# DevBoard.net
KiCad netlist of a schematic drawn in Altium Designer
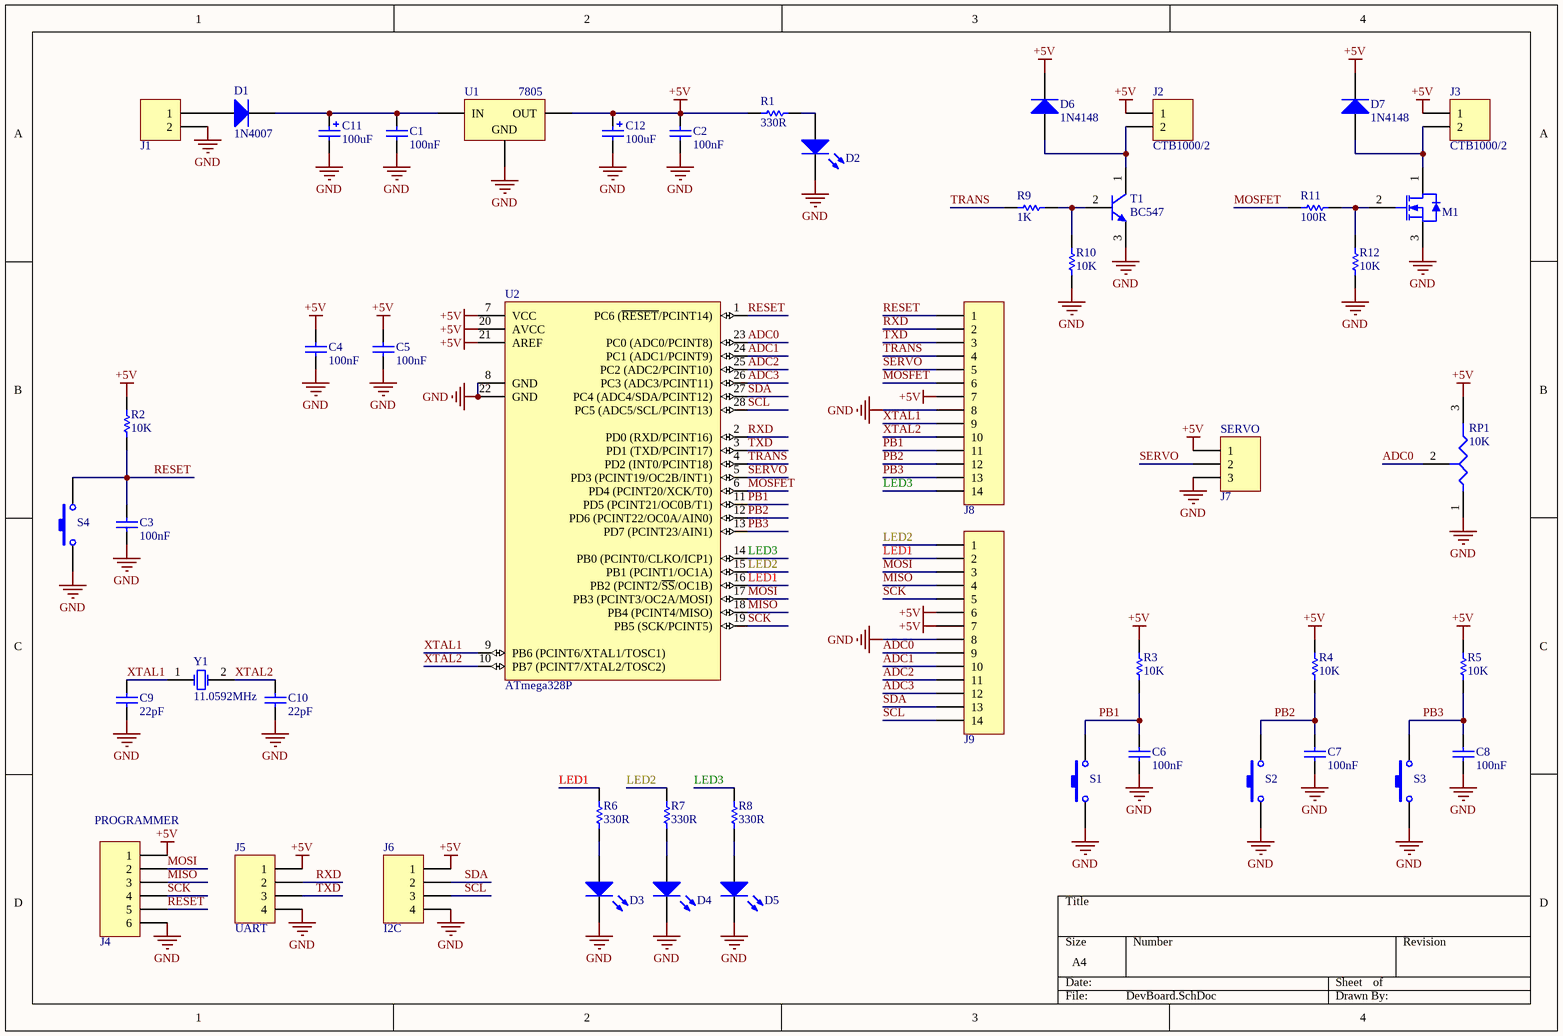
[diagram p0: DevBoard.SchDoc]

(export (version "E")
  (design (tool "Eeschema 10.0.6"))
  (components
    (comp (ref "C1")
      (value "100nF")
      (footprint "RAD-0.1")
      (description "Ceramic Capacitor")
      (libsource (lib "CapacitorsTH") (part "CAP"))
    )
    (comp (ref "C2")
      (value "100nF")
      (footprint "RAD-0.1")
      (description "Ceramic Capacitor")
      (libsource (lib "CapacitorsTH") (part "CAP"))
    )
    (comp (ref "C3")
      (value "100nF")
      (footprint "RAD-0.1")
      (description "Ceramic Capacitor")
      (libsource (lib "CapacitorsTH") (part "CAP"))
    )
    (comp (ref "C4")
      (value "100nF")
      (footprint "RAD-0.1")
      (description "Ceramic Capacitor")
      (libsource (lib "CapacitorsTH") (part "CAP"))
    )
    (comp (ref "C5")
      (value "100nF")
      (footprint "RAD-0.1")
      (description "Ceramic Capacitor")
      (libsource (lib "CapacitorsTH") (part "CAP"))
    )
    (comp (ref "C6")
      (value "100nF")
      (footprint "RAD-0.1")
      (description "Ceramic Capacitor")
      (libsource (lib "CapacitorsTH") (part "CAP"))
    )
    (comp (ref "C7")
      (value "100nF")
      (footprint "RAD-0.1")
      (description "Ceramic Capacitor")
      (libsource (lib "CapacitorsTH") (part "CAP"))
    )
    (comp (ref "C8")
      (value "100nF")
      (footprint "RAD-0.1")
      (description "Ceramic Capacitor")
      (libsource (lib "CapacitorsTH") (part "CAP"))
    )
    (comp (ref "C9")
      (value "22pF")
      (footprint "RAD-0.1")
      (description "Ceramic Capacitor")
      (libsource (lib "CapacitorsTH") (part "CAP"))
    )
    (comp (ref "C10")
      (value "22pF")
      (footprint "RAD-0.1")
      (description "Ceramic Capacitor")
      (libsource (lib "CapacitorsTH") (part "CAP"))
    )
    (comp (ref "C11")
      (value "100uF")
      (footprint "CAP3.5mmX8mm")
      (description "Electrolytic Capacitor")
      (libsource (lib "CapacitorsTH") (part "CAP POL"))
    )
    (comp (ref "C12")
      (value "100uF")
      (footprint "CAP3.5mmX8mm")
      (description "Electrolytic Capacitor")
      (libsource (lib "CapacitorsTH") (part "CAP POL"))
    )
    (comp (ref "D1")
      (value "1N4007")
      (footprint "DO-41")
      (description "Rectifier, 1A, 1000V")
      (libsource (lib "diode_regular") (part "1N4007"))
    )
    (comp (ref "D2")
      (value "Power ON")
      (footprint "LED3mmRED")
      (description "LED")
      (libsource (lib "LED_TH") (part "LED"))
    )
    (comp (ref "D3")
      (value "LED1")
      (footprint "LED3mmRED")
      (description "LED")
      (libsource (lib "LED_TH") (part "LED"))
    )
    (comp (ref "D4")
      (value "LED1")
      (footprint "LED3MMYELLOW")
      (description "LED")
      (libsource (lib "LED_TH") (part "LED"))
    )
    (comp (ref "D5")
      (value "LED1")
      (footprint "LED3MMGREEN")
      (description "LED")
      (libsource (lib "LED_TH") (part "LED"))
    )
    (comp (ref "D6")
      (value "1N4148")
      (footprint "DO-35")
      (description "High Conductance Fast Diode")
      (libsource (lib "diode_regular_20151016") (part "1N4148"))
    )
    (comp (ref "D7")
      (value "1N4148")
      (footprint "DO-35")
      (description "High Conductance Fast Diode")
      (libsource (lib "diode_regular_20151016") (part "1N4148"))
    )
    (comp (ref "J1")
      (value "CTB1000/2")
      (footprint "CTB1000/2")
      (description "CTB1000/2, PCB TERMINAL BLOCK, 5MM, 2WAY")
      (fields (field (name "MANUFACTURER") "CAMDENBOSS"))
      (libsource (lib "") (part "CTB1000/2_1"))
    )
    (comp (ref "J2")
      (value "CTB1000/2")
      (footprint "CTB1000/2")
      (description "CTB1000/2, PCB TERMINAL BLOCK, 5MM, 2WAY")
      (fields (field (name "MANUFACTURER") "CAMDENBOSS"))
      (libsource (lib "clamp_2pin_2015030") (part "CTB1000/2"))
    )
    (comp (ref "J3")
      (value "CTB1000/2")
      (footprint "CTB1000/2")
      (description "CTB1000/2, PCB TERMINAL BLOCK, 5MM, 2WAY")
      (fields (field (name "MANUFACTURER") "CAMDENBOSS"))
      (libsource (lib "clamp_2pin_2015030") (part "CTB1000/2"))
    )
    (comp (ref "J4")
      (value "PROGRAMMER")
      (footprint "HEADER1X6")
      (description "Header, 6-Pin, 1-row")
      (libsource (lib "Header_20150530") (part "HEADER1X6"))
    )
    (comp (ref "J5")
      (value "UART")
      (footprint "HEADER1X4")
      (description "Header, 4-Pin, 1-row")
      (libsource (lib "Header_20150530") (part "HEADER1X4"))
    )
    (comp (ref "J6")
      (value "I2C")
      (footprint "HEADER1X4")
      (description "Header, 4-Pin, 1-row")
      (libsource (lib "Header_20150530") (part "HEADER1X4"))
    )
    (comp (ref "J7")
      (value "SERVO")
      (footprint "HEADER1X3")
      (description "Header, 3-Pin, 1-row")
      (libsource (lib "Header_20150530") (part "HEADER1X3"))
    )
    (comp (ref "J8")
      (value "HEADER1X14")
      (footprint "HEADER1X14")
      (description "Header, 14-pin, 1-row")
      (libsource (lib "Header_20150530") (part "HEADER1X14"))
    )
    (comp (ref "J9")
      (value "HEADER1X14")
      (footprint "HEADER1X14")
      (description "Header, 14-pin, 1-row")
      (libsource (lib "Header_20150530") (part "HEADER1X14"))
    )
    (comp (ref "M1")
      (value "BS170")
      (footprint "TO-92")
      (description "N-Channel MOSFET")
      (libsource (lib "mosfets") (part "BS170"))
    )
    (comp (ref "R1") (value "330R") (footprint "AXIAL-0.3") (libsource (lib "ResistorsTH") (part "Resistor")))
    (comp (ref "R2") (value "10K") (footprint "AXIAL-0.3") (libsource (lib "ResistorsTH") (part "Resistor")))
    (comp (ref "R3") (value "10K") (footprint "AXIAL-0.3") (libsource (lib "ResistorsTH") (part "Resistor")))
    (comp (ref "R4") (value "10K") (footprint "AXIAL-0.3") (libsource (lib "ResistorsTH") (part "Resistor")))
    (comp (ref "R5") (value "10K") (footprint "AXIAL-0.3") (libsource (lib "ResistorsTH") (part "Resistor")))
    (comp (ref "R6") (value "330R") (footprint "AXIAL-0.3") (libsource (lib "ResistorsTH") (part "Resistor")))
    (comp (ref "R7") (value "330R") (footprint "AXIAL-0.3") (libsource (lib "ResistorsTH") (part "Resistor")))
    (comp (ref "R8") (value "330R") (footprint "AXIAL-0.3") (libsource (lib "ResistorsTH") (part "Resistor")))
    (comp (ref "R9") (value "1K") (footprint "AXIAL-0.3") (libsource (lib "ResistorsTH") (part "Resistor")))
    (comp (ref "R10") (value "10K") (footprint "AXIAL-0.3") (libsource (lib "ResistorsTH") (part "Resistor")))
    (comp (ref "R11")
      (value "100R")
      (footprint "AXIAL-0.3")
      (libsource (lib "ResistorsTH") (part "Resistor"))
    )
    (comp (ref "R12") (value "10K") (footprint "AXIAL-0.3") (libsource (lib "ResistorsTH") (part "Resistor")))
    (comp (ref "RP1")
      (value "10K")
      (footprint "HPOT")
      (description "Potentiometer")
      (libsource (lib "potentiometers") (part "POT"))
    )
    (comp (ref "S1")
      (value "SW-PB")
      (footprint "MICROPUSHBUTTON")
      (description "Pushbutton")
      (libsource (lib "switches") (part "SW-PB"))
    )
    (comp (ref "S2")
      (value "SW-PB")
      (footprint "MICROPUSHBUTTON")
      (description "Pushbutton")
      (libsource (lib "switches") (part "SW-PB"))
    )
    (comp (ref "S3")
      (value "SW-PB")
      (footprint "MICROPUSHBUTTON")
      (description "Pushbutton")
      (libsource (lib "switches") (part "SW-PB"))
    )
    (comp (ref "S4")
      (value "SW-PB")
      (footprint "MICROPUSHBUTTON")
      (description "Pushbutton")
      (libsource (lib "switches_20151016") (part "SW-PB"))
    )
    (comp (ref "T1")
      (value "BC547")
      (footprint "TO-92")
      (description "NPN Epitaxial Silicon Transistor")
      (libsource (lib "transistors") (part "BC547"))
    )
    (comp (ref "U1")
      (value "7805")
      (footprint "TO-220L")
      (description "Positive Voltage Regulator, 5V, 1A, TO-220")
      (libsource (lib "Linear_power_regulator_20150714") (part "LM7805"))
    )
    (comp (ref "U2")
      (value "ATmega328P")
      (footprint "28P3")
      (description "8-bit Atmel Microcontroller with 32KB In-System Programmable Flash")
      (libsource (lib "AVR_atmega_20150530") (part "ATmega328P"))
    )
    (comp (ref "Y1")
      (value "11.0592MHz")
      (footprint "TH HC-49S")
      (description "Resonator: quartz")
      (libsource (lib "CrystalQuartz_20150530") (part "Crystal Quartz"))
    )
  )
  (nets
    (net (code "1") (name "+5V") (class "Default")
      (node (ref "C12") (pin "1") (pinfunction "1_1") (pintype "passive"))
      (node (ref "C2") (pin "2") (pinfunction "2_2") (pintype "passive"))
      (node (ref "C4") (pin "2") (pinfunction "2_2") (pintype "passive"))
      (node (ref "C5") (pin "2") (pinfunction "2_2") (pintype "passive"))
      (node (ref "D6") (pin "2") (pinfunction "K_2") (pintype "passive"))
      (node (ref "D7") (pin "2") (pinfunction "K_2") (pintype "passive"))
      (node (ref "J2") (pin "1") (pinfunction "1_1") (pintype "passive"))
      (node (ref "J3") (pin "1") (pinfunction "1_1") (pintype "passive"))
      (node (ref "J4") (pin "1") (pinfunction "1_1") (pintype "passive"))
      (node (ref "J5") (pin "1") (pinfunction "1_1") (pintype "passive"))
      (node (ref "J6") (pin "1") (pinfunction "1_1") (pintype "passive"))
      (node (ref "J7") (pin "1") (pinfunction "1_1") (pintype "passive"))
      (node (ref "J8") (pin "7") (pinfunction "7_7") (pintype "passive"))
      (node (ref "J9") (pin "6") (pinfunction "6_6") (pintype "passive"))
      (node (ref "J9") (pin "7") (pinfunction "7_7") (pintype "passive"))
      (node (ref "R1") (pin "1") (pinfunction "1_1") (pintype "passive"))
      (node (ref "R2") (pin "2") (pinfunction "2_2") (pintype "passive"))
      (node (ref "R3") (pin "2") (pinfunction "2_2") (pintype "passive"))
      (node (ref "R4") (pin "2") (pinfunction "2_2") (pintype "passive"))
      (node (ref "R5") (pin "2") (pinfunction "2_2") (pintype "passive"))
      (node (ref "RP1") (pin "3") (pinfunction "3_3") (pintype "passive"))
      (node (ref "U1") (pin "3") (pinfunction "OUT_3") (pintype "passive"))
      (node (ref "U2") (pin "20") (pinfunction "AVCC_20") (pintype "power_in"))
      (node (ref "U2") (pin "21") (pinfunction "AREF_21") (pintype "passive"))
      (node (ref "U2") (pin "7") (pinfunction "VCC_7") (pintype "power_in"))
    )
    (net (code "2") (name "/ADC0") (class "Default")
      (node (ref "J9") (pin "9") (pinfunction "9_9") (pintype "passive"))
      (node (ref "RP1") (pin "2") (pinfunction "2_2") (pintype "passive"))
      (node (ref "U2") (pin "23") (pinfunction "PC0_(ADC0/PCINT8)_23") (pintype "bidirectional"))
    )
    (net (code "3") (name "/ADC1") (class "Default")
      (node (ref "J9") (pin "10") (pinfunction "10_10") (pintype "passive"))
      (node (ref "U2") (pin "24") (pinfunction "PC1_(ADC1/PCINT9)_24") (pintype "bidirectional"))
    )
    (net (code "4") (name "/ADC2") (class "Default")
      (node (ref "J9") (pin "11") (pinfunction "11_11") (pintype "passive"))
      (node (ref "U2") (pin "25") (pinfunction "PC2_(ADC2/PCINT10)_25") (pintype "bidirectional"))
    )
    (net (code "5") (name "/ADC3") (class "Default")
      (node (ref "J9") (pin "12") (pinfunction "12_12") (pintype "passive"))
      (node (ref "U2") (pin "26") (pinfunction "PC3_(ADC3/PCINT11)_26") (pintype "bidirectional"))
    )
    (net (code "6") (name "/LED1") (class "Default")
      (node (ref "J9") (pin "2") (pinfunction "2_2") (pintype "passive"))
      (node (ref "R6") (pin "2") (pinfunction "2_2") (pintype "passive"))
      (node (ref "U2") (pin "16") (pinfunction "PB2_(PCINT2/~{SS}/OC1B)_16") (pintype "bidirectional"))
    )
    (net (code "7") (name "/LED2") (class "Default")
      (node (ref "J9") (pin "1") (pinfunction "1_1") (pintype "passive"))
      (node (ref "R7") (pin "2") (pinfunction "2_2") (pintype "passive"))
      (node (ref "U2") (pin "15") (pinfunction "PB1_(PCINT1/OC1A)_15") (pintype "bidirectional"))
    )
    (net (code "8") (name "/LED3") (class "Default")
      (node (ref "J8") (pin "14") (pinfunction "14_14") (pintype "passive"))
      (node (ref "R8") (pin "2") (pinfunction "2_2") (pintype "passive"))
      (node (ref "U2") (pin "14") (pinfunction "PB0_(PCINT0/CLKO/ICP1)_14") (pintype "bidirectional"))
    )
    (net (code "9") (name "/MISO") (class "Default")
      (node (ref "J4") (pin "3") (pinfunction "3_3") (pintype "passive"))
      (node (ref "J9") (pin "4") (pinfunction "4_4") (pintype "passive"))
      (node (ref "U2") (pin "18") (pinfunction "PB4_(PCINT4/MISO)_18") (pintype "bidirectional"))
    )
    (net (code "10") (name "/MOSFET") (class "Default")
      (node (ref "J8") (pin "6") (pinfunction "6_6") (pintype "passive"))
      (node (ref "R11") (pin "1") (pinfunction "1_1") (pintype "passive"))
      (node (ref "U2") (pin "6") (pinfunction "PD4_(PCINT20/XCK/T0)_6") (pintype "bidirectional"))
    )
    (net (code "11") (name "/MOSI") (class "Default")
      (node (ref "J4") (pin "2") (pinfunction "2_2") (pintype "passive"))
      (node (ref "J9") (pin "3") (pinfunction "3_3") (pintype "passive"))
      (node (ref "U2") (pin "17") (pinfunction "PB3_(PCINT3/OC2A/MOSI)_17") (pintype "bidirectional"))
    )
    (net (code "12") (name "/PB1") (class "Default")
      (node (ref "C6") (pin "2") (pinfunction "2_2") (pintype "passive"))
      (node (ref "J8") (pin "11") (pinfunction "11_11") (pintype "passive"))
      (node (ref "R3") (pin "1") (pinfunction "1_1") (pintype "passive"))
      (node (ref "S1") (pin "2") (pinfunction "2_2") (pintype "passive"))
      (node (ref "U2") (pin "11") (pinfunction "PD5_(PCINT21/OC0B/T1)_11") (pintype "bidirectional"))
    )
    (net (code "13") (name "/PB2") (class "Default")
      (node (ref "C7") (pin "2") (pinfunction "2_2") (pintype "passive"))
      (node (ref "J8") (pin "12") (pinfunction "12_12") (pintype "passive"))
      (node (ref "R4") (pin "1") (pinfunction "1_1") (pintype "passive"))
      (node (ref "S2") (pin "2") (pinfunction "2_2") (pintype "passive"))
      (node (ref "U2") (pin "12") (pinfunction "PD6_(PCINT22/OC0A/AIN0)_12") (pintype "bidirectional"))
    )
    (net (code "14") (name "/PB3") (class "Default")
      (node (ref "C8") (pin "2") (pinfunction "2_2") (pintype "passive"))
      (node (ref "J8") (pin "13") (pinfunction "13_13") (pintype "passive"))
      (node (ref "R5") (pin "1") (pinfunction "1_1") (pintype "passive"))
      (node (ref "S3") (pin "2") (pinfunction "2_2") (pintype "passive"))
      (node (ref "U2") (pin "13") (pinfunction "PD7_(PCINT23/AIN1)_13") (pintype "bidirectional"))
    )
    (net (code "15") (name "/RESET") (class "Default")
      (node (ref "C3") (pin "2") (pinfunction "2_2") (pintype "passive"))
      (node (ref "J4") (pin "5") (pinfunction "5_5") (pintype "passive"))
      (node (ref "J8") (pin "1") (pinfunction "1_1") (pintype "passive"))
      (node (ref "R2") (pin "1") (pinfunction "1_1") (pintype "passive"))
      (node (ref "S4") (pin "2") (pinfunction "2_2") (pintype "passive"))
      (node (ref "U2") (pin "1") (pinfunction "PC6_(~{RESET}/PCINT14)_1") (pintype "bidirectional"))
    )
    (net (code "16") (name "/RXD") (class "Default")
      (node (ref "J5") (pin "2") (pinfunction "2_2") (pintype "passive"))
      (node (ref "J8") (pin "2") (pinfunction "2_2") (pintype "passive"))
      (node (ref "U2") (pin "2") (pinfunction "PD0_(RXD/PCINT16)_2") (pintype "bidirectional"))
    )
    (net (code "17") (name "/SCK") (class "Default")
      (node (ref "J4") (pin "4") (pinfunction "4_4") (pintype "passive"))
      (node (ref "J9") (pin "5") (pinfunction "5_5") (pintype "passive"))
      (node (ref "U2") (pin "19") (pinfunction "PB5_(SCK/PCINT5)_19") (pintype "bidirectional"))
    )
    (net (code "18") (name "/SCL") (class "Default")
      (node (ref "J6") (pin "3") (pinfunction "3_3") (pintype "passive"))
      (node (ref "J9") (pin "14") (pinfunction "14_14") (pintype "passive"))
      (node (ref "U2") (pin "28") (pinfunction "PC5_(ADC5/SCL/PCINT13)_28") (pintype "bidirectional"))
    )
    (net (code "19") (name "/SDA") (class "Default")
      (node (ref "J6") (pin "2") (pinfunction "2_2") (pintype "passive"))
      (node (ref "J9") (pin "13") (pinfunction "13_13") (pintype "passive"))
      (node (ref "U2") (pin "27") (pinfunction "PC4_(ADC4/SDA/PCINT12)_27") (pintype "bidirectional"))
    )
    (net (code "20") (name "/SERVO") (class "Default")
      (node (ref "J7") (pin "2") (pinfunction "2_2") (pintype "passive"))
      (node (ref "J8") (pin "5") (pinfunction "5_5") (pintype "passive"))
      (node (ref "U2") (pin "5") (pinfunction "PD3_(PCINT19/OC2B/INT1)_5") (pintype "bidirectional"))
    )
    (net (code "21") (name "/TRANS") (class "Default")
      (node (ref "J8") (pin "4") (pinfunction "4_4") (pintype "passive"))
      (node (ref "R9") (pin "2") (pinfunction "2_2") (pintype "passive"))
      (node (ref "U2") (pin "4") (pinfunction "PD2_(INT0/PCINT18)_4") (pintype "bidirectional"))
    )
    (net (code "22") (name "/TXD") (class "Default")
      (node (ref "J5") (pin "3") (pinfunction "3_3") (pintype "passive"))
      (node (ref "J8") (pin "3") (pinfunction "3_3") (pintype "passive"))
      (node (ref "U2") (pin "3") (pinfunction "PD1_(TXD/PCINT17)_3") (pintype "bidirectional"))
    )
    (net (code "23") (name "/XTAL1") (class "Default")
      (node (ref "C9") (pin "2") (pinfunction "2_2") (pintype "passive"))
      (node (ref "J8") (pin "9") (pinfunction "9_9") (pintype "passive"))
      (node (ref "U2") (pin "9") (pinfunction "PB6_(PCINT6/XTAL1/TOSC1)_9") (pintype "bidirectional"))
      (node (ref "Y1") (pin "1") (pinfunction "OSC1_1") (pintype "passive"))
    )
    (net (code "24") (name "/XTAL2") (class "Default")
      (node (ref "C10") (pin "2") (pinfunction "2_2") (pintype "passive"))
      (node (ref "J8") (pin "10") (pinfunction "10_10") (pintype "passive"))
      (node (ref "U2") (pin "10") (pinfunction "PB7_(PCINT7/XTAL2/TOSC2)_10") (pintype "bidirectional"))
      (node (ref "Y1") (pin "2") (pinfunction "OSC2_2") (pintype "passive"))
    )
    (net (code "25") (name "GND") (class "Default")
      (node (ref "C1") (pin "1") (pinfunction "1_1") (pintype "passive"))
      (node (ref "C10") (pin "1") (pinfunction "1_1") (pintype "passive"))
      (node (ref "C11") (pin "2") (pinfunction "2_2") (pintype "passive"))
      (node (ref "C12") (pin "2") (pinfunction "2_2") (pintype "passive"))
      (node (ref "C2") (pin "1") (pinfunction "1_1") (pintype "passive"))
      (node (ref "C3") (pin "1") (pinfunction "1_1") (pintype "passive"))
      (node (ref "C4") (pin "1") (pinfunction "1_1") (pintype "passive"))
      (node (ref "C5") (pin "1") (pinfunction "1_1") (pintype "passive"))
      (node (ref "C6") (pin "1") (pinfunction "1_1") (pintype "passive"))
      (node (ref "C7") (pin "1") (pinfunction "1_1") (pintype "passive"))
      (node (ref "C8") (pin "1") (pinfunction "1_1") (pintype "passive"))
      (node (ref "C9") (pin "1") (pinfunction "1_1") (pintype "passive"))
      (node (ref "D2") (pin "2") (pinfunction "K_2") (pintype "passive"))
      (node (ref "D3") (pin "2") (pinfunction "K_2") (pintype "passive"))
      (node (ref "D4") (pin "2") (pinfunction "K_2") (pintype "passive"))
      (node (ref "D5") (pin "2") (pinfunction "K_2") (pintype "passive"))
      (node (ref "J1") (pin "2") (pinfunction "2_2") (pintype "passive"))
      (node (ref "J4") (pin "6") (pinfunction "6_6") (pintype "passive"))
      (node (ref "J5") (pin "4") (pinfunction "4_4") (pintype "passive"))
      (node (ref "J6") (pin "4") (pinfunction "4_4") (pintype "passive"))
      (node (ref "J7") (pin "3") (pinfunction "3_3") (pintype "passive"))
      (node (ref "J8") (pin "8") (pinfunction "8_8") (pintype "passive"))
      (node (ref "J9") (pin "8") (pinfunction "8_8") (pintype "passive"))
      (node (ref "M1") (pin "3") (pinfunction "S_3") (pintype "passive"))
      (node (ref "R10") (pin "2") (pinfunction "2_2") (pintype "passive"))
      (node (ref "R12") (pin "1") (pinfunction "1_1") (pintype "passive"))
      (node (ref "RP1") (pin "1") (pinfunction "1_1") (pintype "passive"))
      (node (ref "S1") (pin "1") (pinfunction "1_1") (pintype "passive"))
      (node (ref "S2") (pin "1") (pinfunction "1_1") (pintype "passive"))
      (node (ref "S3") (pin "1") (pinfunction "1_1") (pintype "passive"))
      (node (ref "S4") (pin "1") (pinfunction "1_1") (pintype "passive"))
      (node (ref "T1") (pin "3") (pinfunction "E_3") (pintype "passive"))
      (node (ref "U1") (pin "2") (pinfunction "GND_2") (pintype "passive"))
      (node (ref "U2") (pin "22") (pinfunction "GND_22") (pintype "power_in"))
      (node (ref "U2") (pin "8") (pinfunction "GND_8") (pintype "power_in"))
    )
    (net (code "26") (name "Net-(D1-A)") (class "Default")
      (node (ref "D1") (pin "1") (pinfunction "A_1") (pintype "passive"))
      (node (ref "J1") (pin "1") (pinfunction "1_1") (pintype "passive"))
    )
    (net (code "27") (name "Net-(D1-K)") (class "Default")
      (node (ref "C1") (pin "2") (pinfunction "2_2") (pintype "passive"))
      (node (ref "C11") (pin "1") (pinfunction "1_1") (pintype "passive"))
      (node (ref "D1") (pin "2") (pinfunction "K_2") (pintype "passive"))
      (node (ref "U1") (pin "1") (pinfunction "IN_1") (pintype "passive"))
    )
    (net (code "28") (name "Net-(D2-A)") (class "Default")
      (node (ref "D2") (pin "1") (pinfunction "A_1") (pintype "passive"))
      (node (ref "R1") (pin "2") (pinfunction "2_2") (pintype "passive"))
    )
    (net (code "29") (name "Net-(D3-A)") (class "Default")
      (node (ref "D3") (pin "1") (pinfunction "A_1") (pintype "passive"))
      (node (ref "R6") (pin "1") (pinfunction "1_1") (pintype "passive"))
    )
    (net (code "30") (name "Net-(D4-A)") (class "Default")
      (node (ref "D4") (pin "1") (pinfunction "A_1") (pintype "passive"))
      (node (ref "R7") (pin "1") (pinfunction "1_1") (pintype "passive"))
    )
    (net (code "31") (name "Net-(D5-A)") (class "Default")
      (node (ref "D5") (pin "1") (pinfunction "A_1") (pintype "passive"))
      (node (ref "R8") (pin "1") (pinfunction "1_1") (pintype "passive"))
    )
    (net (code "32") (name "Net-(D6-A)") (class "Default")
      (node (ref "D6") (pin "1") (pinfunction "A_1") (pintype "passive"))
      (node (ref "J2") (pin "2") (pinfunction "2_2") (pintype "passive"))
      (node (ref "T1") (pin "1") (pinfunction "C_1") (pintype "passive"))
    )
    (net (code "33") (name "Net-(D7-A)") (class "Default")
      (node (ref "D7") (pin "1") (pinfunction "A_1") (pintype "passive"))
      (node (ref "J3") (pin "2") (pinfunction "2_2") (pintype "passive"))
      (node (ref "M1") (pin "1") (pinfunction "D_1") (pintype "passive"))
    )
    (net (code "34") (name "Net-(M1-G)") (class "Default")
      (node (ref "M1") (pin "2") (pinfunction "G_2") (pintype "passive"))
      (node (ref "R11") (pin "2") (pinfunction "2_2") (pintype "passive"))
      (node (ref "R12") (pin "2") (pinfunction "2_2") (pintype "passive"))
    )
    (net (code "35") (name "Net-(T1-B)") (class "Default")
      (node (ref "R10") (pin "1") (pinfunction "1_1") (pintype "passive"))
      (node (ref "R9") (pin "1") (pinfunction "1_1") (pintype "passive"))
      (node (ref "T1") (pin "2") (pinfunction "B_2") (pintype "passive"))
    )
  )
)
